# GSM_test.net
KiCad netlist of a schematic drawn in Altium Designer
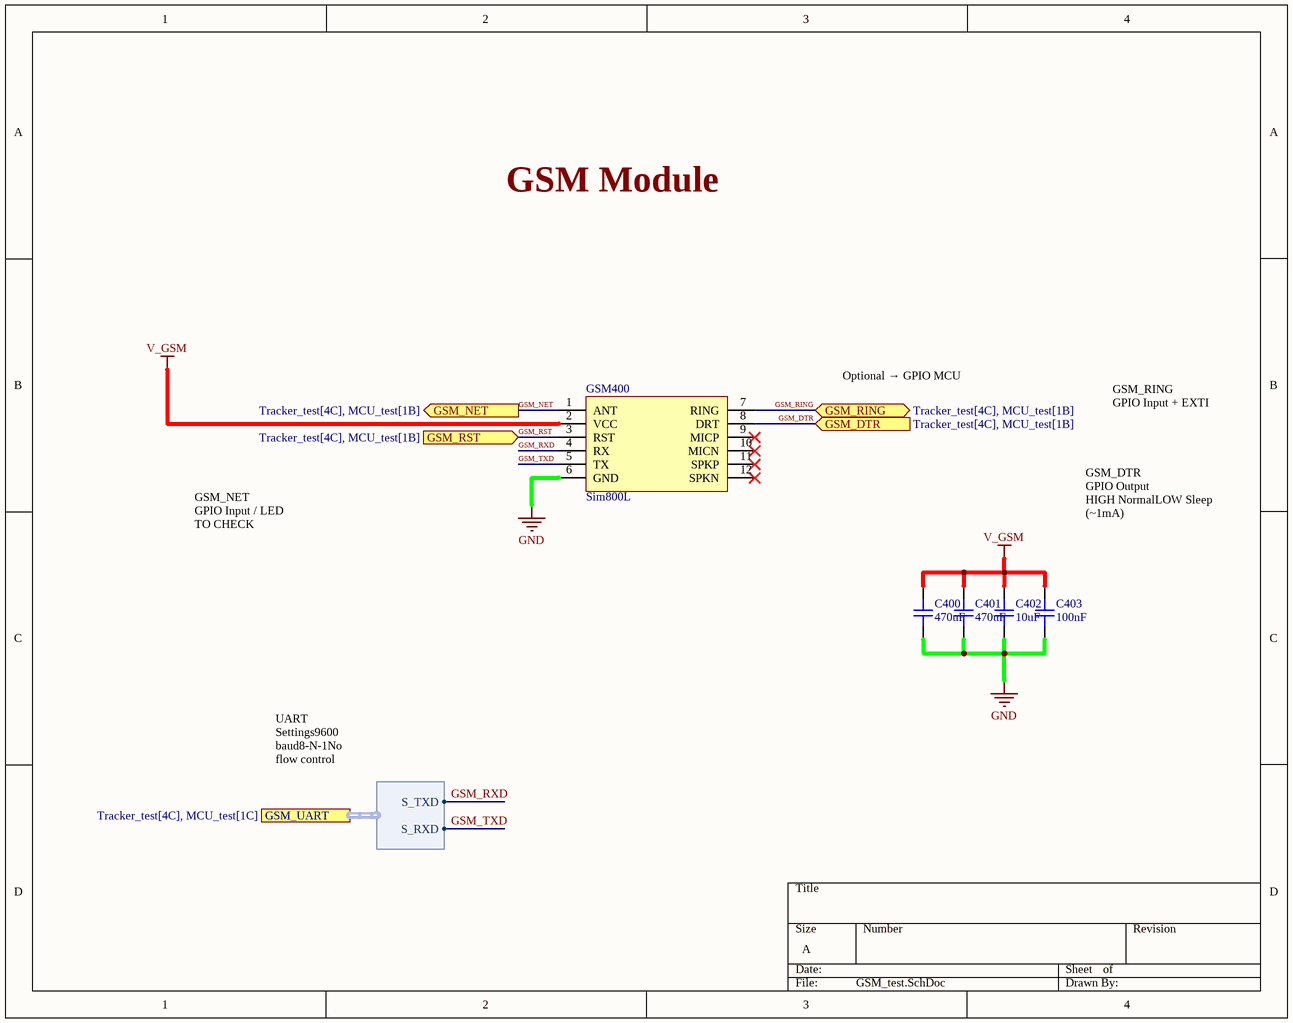
[diagram p0: GSM_test.SchDoc]

(export (version "E")
  (design (tool "Eeschema 10.0.6"))
  (components
    (comp (ref "C400")
      (value "470uF")
      (footprint "CAP_1206")
      (description "Capacitor SMD 1206")
      (libsource (lib "PhilsLab_Library") (part "CAP_1206"))
    )
    (comp (ref "C401")
      (value "470uF")
      (footprint "CAP_1206")
      (description "Capacitor SMD 1206")
      (libsource (lib "PhilsLab_Library") (part "CAP_1206"))
    )
    (comp (ref "C402")
      (value "10uF")
      (footprint "CAP_1206")
      (description "Capacitor SMD 1206")
      (libsource (lib "PhilsLab_Library") (part "CAP_1206"))
    )
    (comp (ref "C403")
      (value "100nF")
      (footprint "CAP_0603")
      (description "Capacitor SMD 0603")
      (libsource (lib "PhilsLab_Library") (part "CAP_0603"))
    )
    (comp (ref "GSM400")
      (value "Sim800L")
      (footprint "Sim800L")
      (libsource (lib "intrgrat_lib") (part "Sim800L"))
    )
  )
  (nets
    (net (code "2") (name "/GSM_DTR") (class "Default")
      (node (ref "GSM400") (pin "8") (pinfunction "DRT_8") (pintype "passive"))
    )
    (net (code "3") (name "/GSM_NET") (class "Default")
      (node (ref "GSM400") (pin "1") (pinfunction "ANT_1") (pintype "passive"))
    )
    (net (code "4") (name "/GSM_RING") (class "Default")
      (node (ref "GSM400") (pin "7") (pinfunction "RING_7") (pintype "passive"))
    )
    (net (code "5") (name "/GSM_RST") (class "Default")
      (node (ref "GSM400") (pin "3") (pinfunction "RST_3") (pintype "passive"))
    )
    (net (code "6") (name "/GSM_RXD") (class "Default")
      (node (ref "GSM400") (pin "4") (pinfunction "RX_4") (pintype "passive"))
    )
    (net (code "7") (name "/GSM_TXD") (class "Default")
      (node (ref "GSM400") (pin "5") (pinfunction "TX_5") (pintype "passive"))
    )
    (net (code "9") (name "GND") (class "Default")
      (node (ref "C400") (pin "1") (pinfunction "1_1") (pintype "passive"))
      (node (ref "C401") (pin "1") (pinfunction "1_1") (pintype "passive"))
      (node (ref "C402") (pin "1") (pinfunction "1_1") (pintype "passive"))
      (node (ref "C403") (pin "1") (pinfunction "1_1") (pintype "passive"))
      (node (ref "GSM400") (pin "6") (pinfunction "GND_6") (pintype "passive"))
    )
    (net (code "10") (name "V_GSM") (class "Default")
      (node (ref "C400") (pin "2") (pinfunction "2_2") (pintype "passive"))
      (node (ref "C401") (pin "2") (pinfunction "2_2") (pintype "passive"))
      (node (ref "C402") (pin "2") (pinfunction "2_2") (pintype "passive"))
      (node (ref "C403") (pin "2") (pinfunction "2_2") (pintype "passive"))
      (node (ref "GSM400") (pin "2") (pinfunction "VCC_2") (pintype "passive"))
    )
    (net (code "11") (name "unconnected-(GSM400-MICN-Pad10)") (class "Default")
      (node (ref "GSM400") (pin "10") (pinfunction "MICN_10") (pintype "passive+no_connect"))
    )
    (net (code "12") (name "unconnected-(GSM400-MICP-Pad9)") (class "Default")
      (node (ref "GSM400") (pin "9") (pinfunction "MICP_9") (pintype "passive+no_connect"))
    )
    (net (code "13") (name "unconnected-(GSM400-SPKN-Pad12)") (class "Default")
      (node (ref "GSM400") (pin "12") (pinfunction "SPKN_12") (pintype "passive+no_connect"))
    )
    (net (code "14") (name "unconnected-(GSM400-SPKP-Pad11)") (class "Default")
      (node (ref "GSM400") (pin "11") (pinfunction "SPKP_11") (pintype "passive+no_connect"))
    )
  )
)
